# JP_SENSOR.net
KiCad netlist of a schematic drawn in EasyEDA Pro
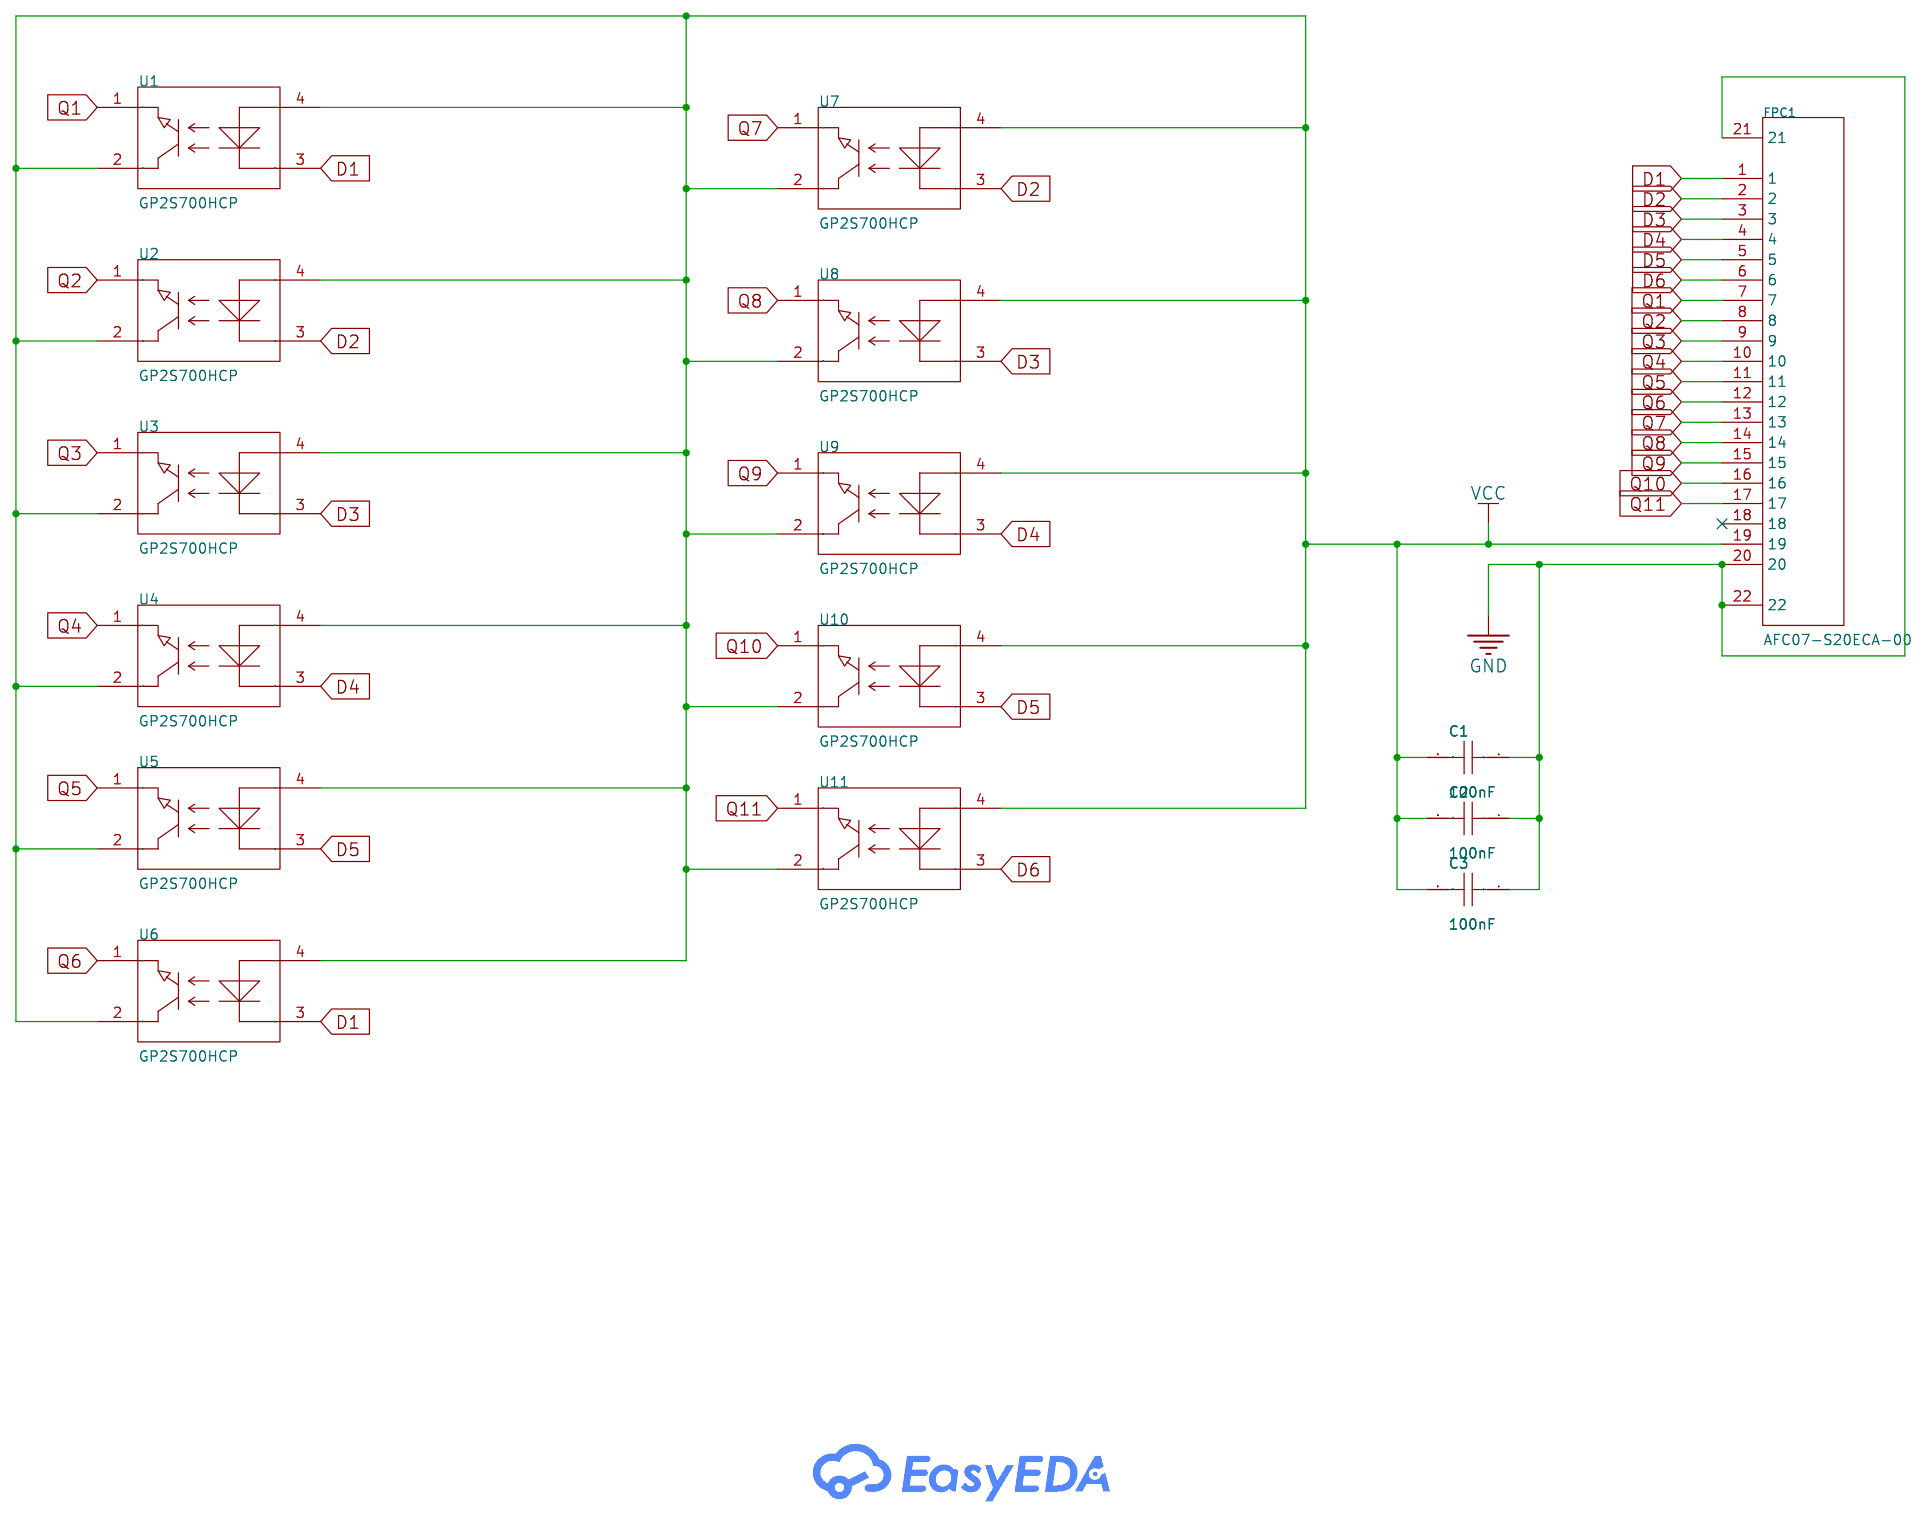
[diagram p0: schematic sheet]

(export (version "E")
  (design (tool "Eeschema 10.0.6"))
  (components
    (comp (ref "C1")
      (value "100nF")
      (footprint "easyedapro:C0603")
      (libsource (lib "easyedapro") (part "CAP"))
    )
    (comp (ref "C2")
      (value "100nF")
      (footprint "easyedapro:C0603")
      (libsource (lib "easyedapro") (part "CAP"))
    )
    (comp (ref "C3")
      (value "100nF")
      (footprint "easyedapro:C0603")
      (libsource (lib "easyedapro") (part "CAP"))
    )
    (comp (ref "FPC1")
      (value "AFC07-S20ECA-00")
      (footprint "easyedapro:FPC-SMD_AFC07-S20ECA-00")
      (fields (field (name "Manufacturer") "JS(钜硕电子)"))
      (libsource (lib "easyedapro") (part "AFC07-S20ECA-00"))
    )
    (comp (ref "U1")
      (value "GP2S700HCP")
      (footprint "easyedapro:OPTO-SMD_GP2S700HCP")
      (description "Sensing Distance:5.5mm Collector Current (Max):20mA")
      (fields (field (name "Manufacturer") "SHARP(夏普)"))
      (libsource (lib "easyedapro") (part "GP2S700HCP"))
    )
    (comp (ref "U2")
      (value "GP2S700HCP")
      (footprint "easyedapro:OPTO-SMD_GP2S700HCP")
      (description "Sensing Distance:5.5mm Collector Current (Max):20mA")
      (fields (field (name "Manufacturer") "SHARP(夏普)"))
      (libsource (lib "easyedapro") (part "GP2S700HCP"))
    )
    (comp (ref "U3")
      (value "GP2S700HCP")
      (footprint "easyedapro:OPTO-SMD_GP2S700HCP")
      (description "Sensing Distance:5.5mm Collector Current (Max):20mA")
      (fields (field (name "Manufacturer") "SHARP(夏普)"))
      (libsource (lib "easyedapro") (part "GP2S700HCP"))
    )
    (comp (ref "U4")
      (value "GP2S700HCP")
      (footprint "easyedapro:OPTO-SMD_GP2S700HCP")
      (description "Sensing Distance:5.5mm Collector Current (Max):20mA")
      (fields (field (name "Manufacturer") "SHARP(夏普)"))
      (libsource (lib "easyedapro") (part "GP2S700HCP"))
    )
    (comp (ref "U5")
      (value "GP2S700HCP")
      (footprint "easyedapro:OPTO-SMD_GP2S700HCP")
      (description "Sensing Distance:5.5mm Collector Current (Max):20mA")
      (fields (field (name "Manufacturer") "SHARP(夏普)"))
      (libsource (lib "easyedapro") (part "GP2S700HCP"))
    )
    (comp (ref "U6")
      (value "GP2S700HCP")
      (footprint "easyedapro:OPTO-SMD_GP2S700HCP")
      (description "Sensing Distance:5.5mm Collector Current (Max):20mA")
      (fields (field (name "Manufacturer") "SHARP(夏普)"))
      (libsource (lib "easyedapro") (part "GP2S700HCP"))
    )
    (comp (ref "U7")
      (value "GP2S700HCP")
      (footprint "easyedapro:OPTO-SMD_GP2S700HCP")
      (description "Sensing Distance:5.5mm Collector Current (Max):20mA")
      (fields (field (name "Manufacturer") "SHARP(夏普)"))
      (libsource (lib "easyedapro") (part "GP2S700HCP"))
    )
    (comp (ref "U8")
      (value "GP2S700HCP")
      (footprint "easyedapro:OPTO-SMD_GP2S700HCP")
      (description "Sensing Distance:5.5mm Collector Current (Max):20mA")
      (fields (field (name "Manufacturer") "SHARP(夏普)"))
      (libsource (lib "easyedapro") (part "GP2S700HCP"))
    )
    (comp (ref "U9")
      (value "GP2S700HCP")
      (footprint "easyedapro:OPTO-SMD_GP2S700HCP")
      (description "Sensing Distance:5.5mm Collector Current (Max):20mA")
      (fields (field (name "Manufacturer") "SHARP(夏普)"))
      (libsource (lib "easyedapro") (part "GP2S700HCP"))
    )
    (comp (ref "U10")
      (value "GP2S700HCP")
      (footprint "easyedapro:OPTO-SMD_GP2S700HCP")
      (description "Sensing Distance:5.5mm Collector Current (Max):20mA")
      (fields (field (name "Manufacturer") "SHARP(夏普)"))
      (libsource (lib "easyedapro") (part "GP2S700HCP"))
    )
    (comp (ref "U11")
      (value "GP2S700HCP")
      (footprint "easyedapro:OPTO-SMD_GP2S700HCP")
      (description "Sensing Distance:5.5mm Collector Current (Max):20mA")
      (fields (field (name "Manufacturer") "SHARP(夏普)"))
      (libsource (lib "easyedapro") (part "GP2S700HCP"))
    )
  )
  (nets
    (net (code "1") (name "D1") (class "Default")
      (node (ref "FPC1") (pin "1") (pinfunction "1_1") (pintype "input"))
      (node (ref "U1") (pin "3") (pinfunction "3_3") (pintype "input"))
      (node (ref "U6") (pin "3") (pinfunction "3_3") (pintype "input"))
    )
    (net (code "2") (name "D2") (class "Default")
      (node (ref "FPC1") (pin "2") (pinfunction "2_2") (pintype "input"))
      (node (ref "U2") (pin "3") (pinfunction "3_3") (pintype "input"))
      (node (ref "U7") (pin "3") (pinfunction "3_3") (pintype "input"))
    )
    (net (code "3") (name "D3") (class "Default")
      (node (ref "FPC1") (pin "3") (pinfunction "3_3") (pintype "input"))
      (node (ref "U3") (pin "3") (pinfunction "3_3") (pintype "input"))
      (node (ref "U8") (pin "3") (pinfunction "3_3") (pintype "input"))
    )
    (net (code "4") (name "D4") (class "Default")
      (node (ref "FPC1") (pin "4") (pinfunction "4_4") (pintype "input"))
      (node (ref "U4") (pin "3") (pinfunction "3_3") (pintype "input"))
      (node (ref "U9") (pin "3") (pinfunction "3_3") (pintype "input"))
    )
    (net (code "5") (name "D5") (class "Default")
      (node (ref "FPC1") (pin "5") (pinfunction "5_5") (pintype "input"))
      (node (ref "U10") (pin "3") (pinfunction "3_3") (pintype "input"))
      (node (ref "U5") (pin "3") (pinfunction "3_3") (pintype "input"))
    )
    (net (code "6") (name "D6") (class "Default")
      (node (ref "FPC1") (pin "6") (pinfunction "6_6") (pintype "input"))
      (node (ref "U11") (pin "3") (pinfunction "3_3") (pintype "input"))
    )
    (net (code "7") (name "GND") (class "Default")
      (node (ref "C1") (pin "1") (pinfunction "1_1") (pintype "input"))
      (node (ref "C2") (pin "1") (pinfunction "1_1") (pintype "input"))
      (node (ref "C3") (pin "1") (pinfunction "1_1") (pintype "input"))
      (node (ref "FPC1") (pin "20") (pinfunction "20_20") (pintype "input"))
      (node (ref "FPC1") (pin "21") (pinfunction "21_21") (pintype "input"))
      (node (ref "FPC1") (pin "22") (pinfunction "22_22") (pintype "input"))
    )
    (net (code "8") (name "Q1") (class "Default")
      (node (ref "FPC1") (pin "7") (pinfunction "7_7") (pintype "input"))
      (node (ref "U1") (pin "1") (pinfunction "1_1") (pintype "input"))
    )
    (net (code "9") (name "Q2") (class "Default")
      (node (ref "FPC1") (pin "8") (pinfunction "8_8") (pintype "input"))
      (node (ref "U2") (pin "1") (pinfunction "1_1") (pintype "input"))
    )
    (net (code "10") (name "Q3") (class "Default")
      (node (ref "FPC1") (pin "9") (pinfunction "9_9") (pintype "input"))
      (node (ref "U3") (pin "1") (pinfunction "1_1") (pintype "input"))
    )
    (net (code "11") (name "Q4") (class "Default")
      (node (ref "FPC1") (pin "10") (pinfunction "10_10") (pintype "input"))
      (node (ref "U4") (pin "1") (pinfunction "1_1") (pintype "input"))
    )
    (net (code "12") (name "Q5") (class "Default")
      (node (ref "FPC1") (pin "11") (pinfunction "11_11") (pintype "input"))
      (node (ref "U5") (pin "1") (pinfunction "1_1") (pintype "input"))
    )
    (net (code "13") (name "Q6") (class "Default")
      (node (ref "FPC1") (pin "12") (pinfunction "12_12") (pintype "input"))
      (node (ref "U6") (pin "1") (pinfunction "1_1") (pintype "input"))
    )
    (net (code "14") (name "Q7") (class "Default")
      (node (ref "FPC1") (pin "13") (pinfunction "13_13") (pintype "input"))
      (node (ref "U7") (pin "1") (pinfunction "1_1") (pintype "input"))
    )
    (net (code "15") (name "Q8") (class "Default")
      (node (ref "FPC1") (pin "14") (pinfunction "14_14") (pintype "input"))
      (node (ref "U8") (pin "1") (pinfunction "1_1") (pintype "input"))
    )
    (net (code "16") (name "Q9") (class "Default")
      (node (ref "FPC1") (pin "15") (pinfunction "15_15") (pintype "input"))
      (node (ref "U9") (pin "1") (pinfunction "1_1") (pintype "input"))
    )
    (net (code "17") (name "Q10") (class "Default")
      (node (ref "FPC1") (pin "16") (pinfunction "16_16") (pintype "input"))
      (node (ref "U10") (pin "1") (pinfunction "1_1") (pintype "input"))
    )
    (net (code "18") (name "Q11") (class "Default")
      (node (ref "FPC1") (pin "17") (pinfunction "17_17") (pintype "input"))
      (node (ref "U11") (pin "1") (pinfunction "1_1") (pintype "input"))
    )
    (net (code "19") (name "VCC") (class "Default")
      (node (ref "C1") (pin "2") (pinfunction "2_2") (pintype "input"))
      (node (ref "C2") (pin "2") (pinfunction "2_2") (pintype "input"))
      (node (ref "C3") (pin "2") (pinfunction "2_2") (pintype "input"))
      (node (ref "FPC1") (pin "19") (pinfunction "19_19") (pintype "input"))
      (node (ref "U1") (pin "2") (pinfunction "2_2") (pintype "input"))
      (node (ref "U1") (pin "4") (pinfunction "4_4") (pintype "input"))
      (node (ref "U10") (pin "2") (pinfunction "2_2") (pintype "input"))
      (node (ref "U10") (pin "4") (pinfunction "4_4") (pintype "input"))
      (node (ref "U11") (pin "2") (pinfunction "2_2") (pintype "input"))
      (node (ref "U11") (pin "4") (pinfunction "4_4") (pintype "input"))
      (node (ref "U2") (pin "2") (pinfunction "2_2") (pintype "input"))
      (node (ref "U2") (pin "4") (pinfunction "4_4") (pintype "input"))
      (node (ref "U3") (pin "2") (pinfunction "2_2") (pintype "input"))
      (node (ref "U3") (pin "4") (pinfunction "4_4") (pintype "input"))
      (node (ref "U4") (pin "2") (pinfunction "2_2") (pintype "input"))
      (node (ref "U4") (pin "4") (pinfunction "4_4") (pintype "input"))
      (node (ref "U5") (pin "2") (pinfunction "2_2") (pintype "input"))
      (node (ref "U5") (pin "4") (pinfunction "4_4") (pintype "input"))
      (node (ref "U6") (pin "2") (pinfunction "2_2") (pintype "input"))
      (node (ref "U6") (pin "4") (pinfunction "4_4") (pintype "input"))
      (node (ref "U7") (pin "2") (pinfunction "2_2") (pintype "input"))
      (node (ref "U7") (pin "4") (pinfunction "4_4") (pintype "input"))
      (node (ref "U8") (pin "2") (pinfunction "2_2") (pintype "input"))
      (node (ref "U8") (pin "4") (pinfunction "4_4") (pintype "input"))
      (node (ref "U9") (pin "2") (pinfunction "2_2") (pintype "input"))
      (node (ref "U9") (pin "4") (pinfunction "4_4") (pintype "input"))
    )
    (net (code "20") (name "unconnected-(FPC1-Pad18)") (class "Default")
      (node (ref "FPC1") (pin "18") (pinfunction "18_18") (pintype "input+no_connect"))
    )
  )
)
